# Sonda_wzmacniacz.net
KiCad netlist of a schematic drawn in Altium Designer
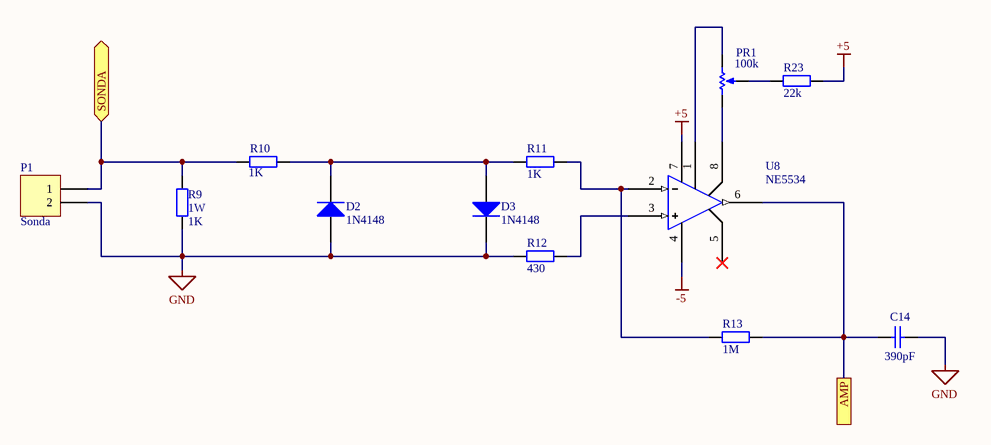
[diagram p0: Sonda+wzmacniacz.SchDoc]

(export (version "E")
  (design (tool "Eeschema 10.0.6"))
  (components
    (comp (ref "C14")
      (value "390pF")
      (footprint "RAD-0.3")
      (description "Capacitor")
      (fields (field (name "Comment") "CL10B391KB8NNNC@TME") (field (name "PUBLISHER") "Altium Limited"))
      (libsource (lib "Miscellaneous Devices") (part "Cap"))
    )
    (comp (ref "D2")
      (value "1N4148")
      (footprint "DIOD-SOD323-2-A_V")
      (libsource (lib "Altium Content Vault") (part "D-AK-2"))
    )
    (comp (ref "D3")
      (value "1N4148")
      (footprint "DIOD-SOD323-2-A_V")
      (libsource (lib "Altium Content Vault") (part "D-AK-2"))
    )
    (comp (ref "P1")
      (value "Sonda")
      (footprint "HDR1X2")
      (description "Header, 2-Pin")
      (fields (field (name "PUBLISHER") "Altium Limited"))
      (libsource (lib "Miscellaneous Connectors") (part "Header 2"))
    )
    (comp (ref "PR1")
      (value "T910Y-100K@TME")
      (footprint "BOUR-3296W")
      (fields (field (name "RESISTANCE") "100k") (field (name "TOLERANCE") "1%"))
      (libsource (lib "Altium Content Vault") (part "RES-POT-3"))
    )
    (comp (ref "R9")
      (value "1W")
      (footprint "AXIAL-0.4")
      (description "Resistor\r\nHP06W2J0102T5E")
      (fields (field (name "ALTIUM_VALUE") "1K") (field (name "PUBLISHER") "Altium Limited"))
      (libsource (lib "") (part "Res2_1"))
    )
    (comp (ref "R10")
      (value "1K")
      (footprint "AXIAL-0.4")
      (description "Resistor")
      (fields (field (name "Comment") "1206S4J0102T5E@TME") (field (name "PUBLISHER") "Altium Limited"))
      (libsource (lib "Miscellaneous Devices") (part "Res2"))
    )
    (comp (ref "R11")
      (value "1K")
      (footprint "AXIAL-0.4")
      (description "Resistor")
      (fields (field (name "Comment") "1206S4J0102T5E@TME") (field (name "PUBLISHER") "Altium Limited"))
      (libsource (lib "Miscellaneous Devices") (part "Res2"))
    )
    (comp (ref "R12")
      (value "430")
      (footprint "AXIAL-0.4")
      (description "Resistor")
      (fields (field (name "Comment") "1206S4J0102T5E@TME") (field (name "PUBLISHER") "Altium Limited"))
      (libsource (lib "Miscellaneous Devices") (part "Res2"))
    )
    (comp (ref "R13")
      (value "1M")
      (footprint "AXIAL-0.4")
      (description "Resistor")
      (fields (field (name "Comment") "1206S4J0105T5E@TME") (field (name "PUBLISHER") "Altium Limited"))
      (libsource (lib "Miscellaneous Devices") (part "Res2"))
    )
    (comp (ref "R23")
      (value "22k")
      (footprint "AXIAL-0.4")
      (description "Resistor")
      (fields (field (name "Comment") "RC1206FR-0722KL@TME") (field (name "PUBLISHER") "Altium Limited"))
      (libsource (lib "Miscellaneous Devices") (part "Res2"))
    )
    (comp (ref "U8") (value "NE5534") (libsource (lib "MetalDetLibrary") (part "NE5534")))
  )
  (nets
    (net (code "1") (name "+5") (class "Default")
      (node (ref "R23") (pin "2") (pinfunction "2_2") (pintype "passive"))
      (node (ref "U8") (pin "7") (pinfunction "VCC+_7") (pintype "power_in"))
    )
    (net (code "2") (name "-5") (class "Default")
      (node (ref "U8") (pin "4") (pinfunction "VCC-_4") (pintype "power_in"))
    )
    (net (code "3") (name "/AMP") (class "Default")
      (node (ref "C14") (pin "2") (pinfunction "2_2") (pintype "passive"))
      (node (ref "R13") (pin "2") (pinfunction "2_2") (pintype "passive"))
      (node (ref "U8") (pin "6") (pinfunction "OUT_6") (pintype "output"))
    )
    (net (code "4") (name "/SONDA") (class "Default")
      (node (ref "P1") (pin "1") (pinfunction "1_1") (pintype "passive"))
      (node (ref "R10") (pin "1") (pinfunction "1_1") (pintype "passive"))
      (node (ref "R9") (pin "2") (pinfunction "2_2") (pintype "passive"))
    )
    (net (code "5") (name "GND") (class "Default")
      (node (ref "C14") (pin "1") (pinfunction "1_1") (pintype "passive"))
      (node (ref "D2") (pin "1") (pinfunction "A_1") (pintype "passive"))
      (node (ref "D3") (pin "2") (pinfunction "K_2") (pintype "passive"))
      (node (ref "P1") (pin "2") (pinfunction "2_2") (pintype "passive"))
      (node (ref "R12") (pin "1") (pinfunction "1_1") (pintype "passive"))
      (node (ref "R9") (pin "1") (pinfunction "1_1") (pintype "passive"))
    )
    (net (code "6") (name "Net-(D2-K)") (class "Default")
      (node (ref "D2") (pin "2") (pinfunction "K_2") (pintype "passive"))
      (node (ref "D3") (pin "1") (pinfunction "A_1") (pintype "passive"))
      (node (ref "R10") (pin "2") (pinfunction "2_2") (pintype "passive"))
      (node (ref "R11") (pin "1") (pinfunction "1_1") (pintype "passive"))
    )
    (net (code "7") (name "Net-(PR1-CCW)") (class "Default")
      (node (ref "PR1") (pin "1") (pinfunction "CCW_1") (pintype "passive"))
      (node (ref "U8") (pin "8") (pinfunction "COMP/BAL_8") (pintype "passive"))
    )
    (net (code "8") (name "Net-(PR1-CW)") (class "Default")
      (node (ref "PR1") (pin "3") (pinfunction "CW_3") (pintype "passive"))
      (node (ref "U8") (pin "1") (pinfunction "BALANCE_1") (pintype "passive"))
    )
    (net (code "9") (name "Net-(PR1-S)") (class "Default")
      (node (ref "PR1") (pin "2") (pinfunction "S_2") (pintype "passive"))
      (node (ref "R23") (pin "1") (pinfunction "1_1") (pintype "passive"))
    )
    (net (code "10") (name "Net-(U8-IN+)") (class "Default")
      (node (ref "R12") (pin "2") (pinfunction "2_2") (pintype "passive"))
      (node (ref "U8") (pin "3") (pinfunction "IN+_3") (pintype "input"))
    )
    (net (code "11") (name "Net-(U8-IN-)") (class "Default")
      (node (ref "R11") (pin "2") (pinfunction "2_2") (pintype "passive"))
      (node (ref "R13") (pin "1") (pinfunction "1_1") (pintype "passive"))
      (node (ref "U8") (pin "2") (pinfunction "IN-_2") (pintype "input"))
    )
    (net (code "12") (name "unconnected-(U8-COMP-Pad5)") (class "Default")
      (node (ref "U8") (pin "5") (pinfunction "COMP_5") (pintype "passive+no_connect"))
    )
  )
)
